# Robot_Led_Stripe_1_25mm.net
KiCad netlist of a schematic drawn in EasyEDA
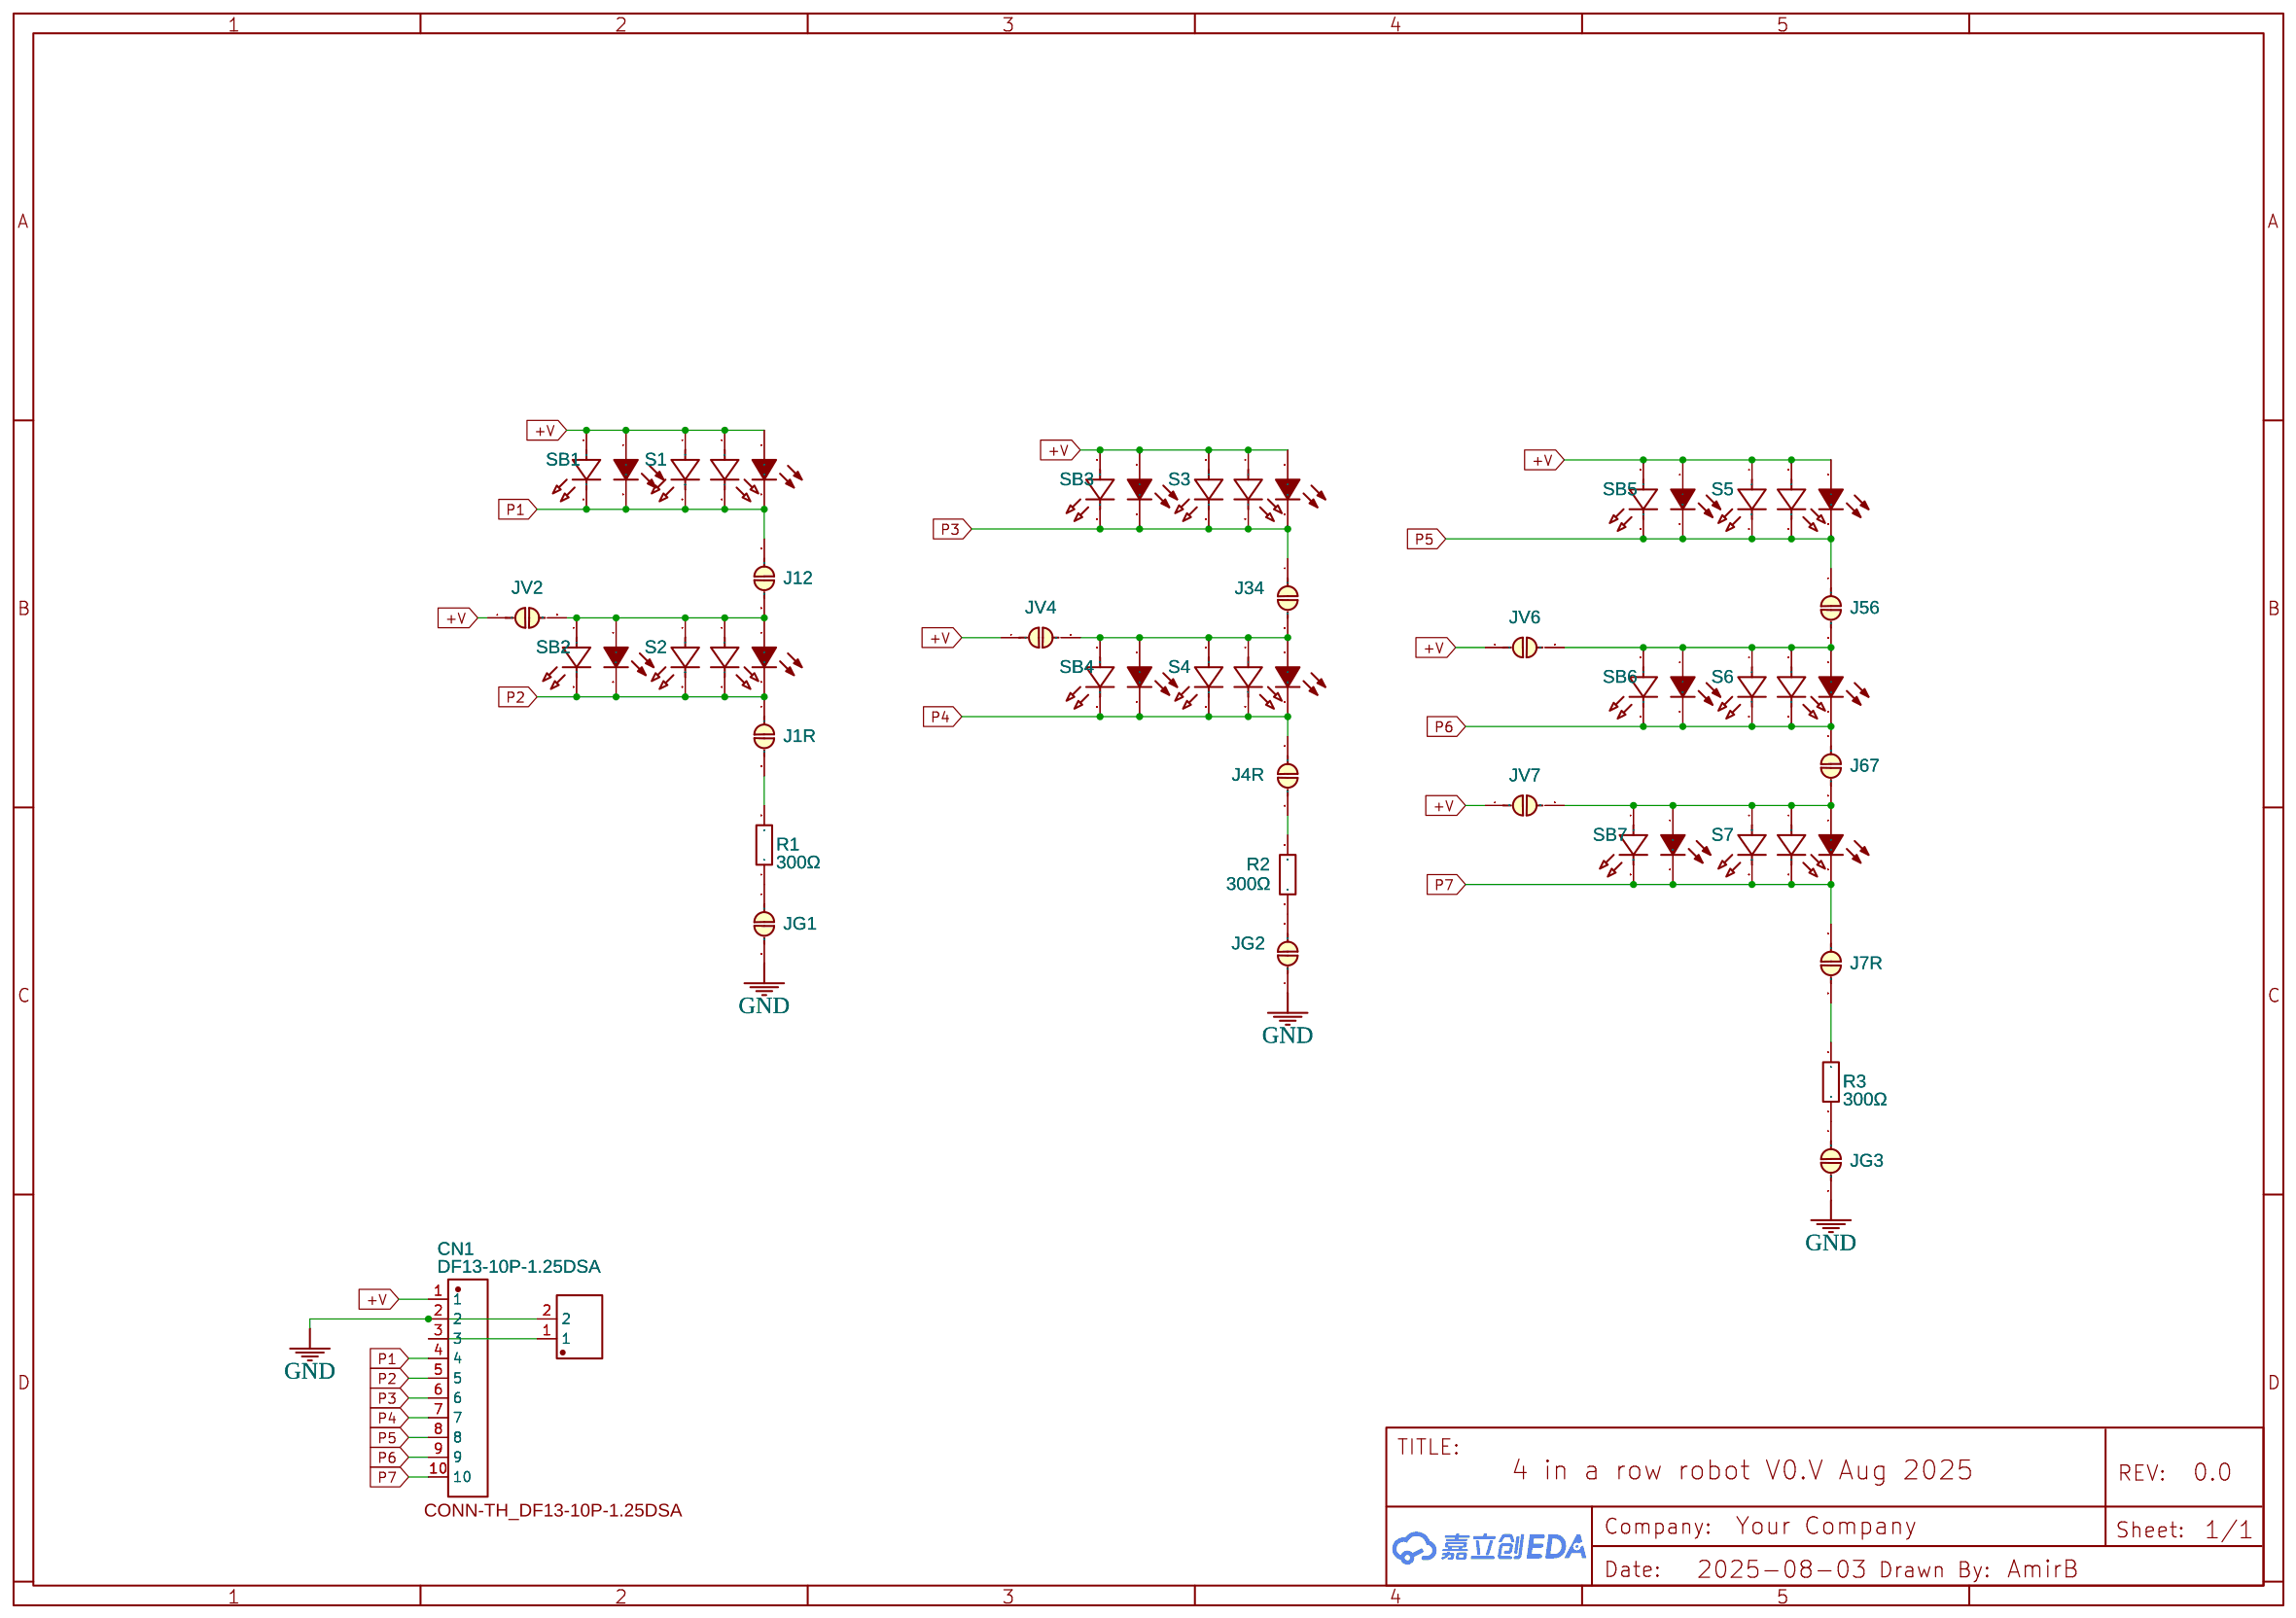
[diagram p0: schematic sheet]

(export (version "E")
  (design (tool "Eeschema 10.0.6"))
  (components
    (comp (ref "CN1")
      (value "DF13-10P-1.25DSA")
      (fields (field (name "Manufacturer") "HRS(广濑)"))
      (libsource (lib "") (part "DF13-10P-1.25DSA"))
    )
    (comp (ref "ECON1")
      (value "KF2510-2A")
      (fields (field (name "BOM_Supplier Part") "C27543"))
      (libsource (lib "") (part "KF2510-2A"))
    )
    (comp (ref "J1R") (value "J1R") (libsource (lib "") (part "JUMPER-SMT_2_5")))
    (comp (ref "J4R") (value "J4R") (libsource (lib "") (part "JUMPER-SMT_2_4")))
    (comp (ref "J7R") (value "J7R") (libsource (lib "") (part "JUMPER-SMT_2_3")))
    (comp (ref "J12") (value "J1") (libsource (lib "") (part "JUMPER-SMT_2_1")))
    (comp (ref "J34") (value "J34") (libsource (lib "") (part "JUMPER-SMT_2_1")))
    (comp (ref "J56") (value "J56") (libsource (lib "") (part "JUMPER-SMT_2_1")))
    (comp (ref "J67") (value "J67") (libsource (lib "") (part "JUMPER-SMT_2_1")))
    (comp (ref "JG1") (value "JG3") (libsource (lib "") (part "JUMPER-SMT_2_2")))
    (comp (ref "JG2") (value "JG3") (libsource (lib "") (part "JUMPER-SMT_2_2")))
    (comp (ref "JG3") (value "JG3") (libsource (lib "") (part "JUMPER-SMT_2_2")))
    (comp (ref "JV2") (value "JV1") (libsource (lib "") (part "JUMPER-SMT_2")))
    (comp (ref "JV4") (value "JV1") (libsource (lib "") (part "JUMPER-SMT_2")))
    (comp (ref "JV6") (value "JV1") (libsource (lib "") (part "JUMPER-SMT_2")))
    (comp (ref "JV7") (value "JV1") (libsource (lib "") (part "JUMPER-SMT_2")))
    (comp (ref "L1")
      (value "LED")
      (fields
        (field (name "BOM_Manufacturer Part") "19-217/BHC-ZL1M2RY/3T")
        (field (name "BOM_Supplier Part") "C72041")
      )
      (libsource (lib "") (part "19-217/BHC-ZL1M2RY/3T"))
    )
    (comp (ref "L2")
      (value "LED")
      (fields
        (field (name "BOM_Manufacturer Part") "19-217/BHC-ZL1M2RY/3T")
        (field (name "BOM_Supplier Part") "C72041")
      )
      (libsource (lib "") (part "19-217/BHC-ZL1M2RY/3T"))
    )
    (comp (ref "L3")
      (value "LED")
      (fields
        (field (name "BOM_Manufacturer Part") "19-217/BHC-ZL1M2RY/3T")
        (field (name "BOM_Supplier Part") "C72041")
      )
      (libsource (lib "") (part "19-217/BHC-ZL1M2RY/3T"))
    )
    (comp (ref "L4")
      (value "LED")
      (fields
        (field (name "BOM_Manufacturer Part") "19-217/BHC-ZL1M2RY/3T")
        (field (name "BOM_Supplier Part") "C72041")
      )
      (libsource (lib "") (part "19-217/BHC-ZL1M2RY/3T"))
    )
    (comp (ref "L5")
      (value "LED")
      (fields
        (field (name "BOM_Manufacturer Part") "19-217/BHC-ZL1M2RY/3T")
        (field (name "BOM_Supplier Part") "C72041")
      )
      (libsource (lib "") (part "19-217/BHC-ZL1M2RY/3T"))
    )
    (comp (ref "L6")
      (value "LED")
      (fields
        (field (name "BOM_Manufacturer Part") "19-217/BHC-ZL1M2RY/3T")
        (field (name "BOM_Supplier Part") "C72041")
      )
      (libsource (lib "") (part "19-217/BHC-ZL1M2RY/3T"))
    )
    (comp (ref "L7")
      (value "LED")
      (fields
        (field (name "BOM_Manufacturer Part") "19-217/BHC-ZL1M2RY/3T")
        (field (name "BOM_Supplier Part") "C72041")
      )
      (libsource (lib "") (part "19-217/BHC-ZL1M2RY/3T"))
    )
    (comp (ref "LB1")
      (value "LED")
      (fields
        (field (name "BOM_Manufacturer Part") "19-217/BHC-ZL1M2RY/3T")
        (field (name "BOM_Supplier Part") "C72041")
      )
      (libsource (lib "") (part "19-217/BHC-ZL1M2RY/3T_1"))
    )
    (comp (ref "LB2")
      (value "LED")
      (fields
        (field (name "BOM_Manufacturer Part") "19-217/BHC-ZL1M2RY/3T")
        (field (name "BOM_Supplier Part") "C72041")
      )
      (libsource (lib "") (part "19-217/BHC-ZL1M2RY/3T_1"))
    )
    (comp (ref "LB3")
      (value "LED")
      (fields
        (field (name "BOM_Manufacturer Part") "19-217/BHC-ZL1M2RY/3T")
        (field (name "BOM_Supplier Part") "C72041")
      )
      (libsource (lib "") (part "19-217/BHC-ZL1M2RY/3T_1"))
    )
    (comp (ref "LB4")
      (value "LED")
      (fields
        (field (name "BOM_Manufacturer Part") "19-217/BHC-ZL1M2RY/3T")
        (field (name "BOM_Supplier Part") "C72041")
      )
      (libsource (lib "") (part "19-217/BHC-ZL1M2RY/3T_1"))
    )
    (comp (ref "LB5")
      (value "LED")
      (fields
        (field (name "BOM_Manufacturer Part") "19-217/BHC-ZL1M2RY/3T")
        (field (name "BOM_Supplier Part") "C72041")
      )
      (libsource (lib "") (part "19-217/BHC-ZL1M2RY/3T_1"))
    )
    (comp (ref "LB6")
      (value "LED")
      (fields
        (field (name "BOM_Manufacturer Part") "19-217/BHC-ZL1M2RY/3T")
        (field (name "BOM_Supplier Part") "C72041")
      )
      (libsource (lib "") (part "19-217/BHC-ZL1M2RY/3T_1"))
    )
    (comp (ref "LB7")
      (value "LED")
      (fields
        (field (name "BOM_Manufacturer Part") "19-217/BHC-ZL1M2RY/3T")
        (field (name "BOM_Supplier Part") "C72041")
      )
      (libsource (lib "") (part "19-217/BHC-ZL1M2RY/3T_1"))
    )
    (comp (ref "R1")
      (value "300Ω")
      (fields
        (field (name "Manufacturer Part") "0603WAF3000T5E")
        (field (name "Manufacturer") "UNI-ROYAL(厚声)")
      )
      (libsource (lib "") (part "0603WAF3000T5E"))
    )
    (comp (ref "R2")
      (value "300Ω")
      (fields
        (field (name "Manufacturer Part") "0603WAF3000T5E")
        (field (name "Manufacturer") "UNI-ROYAL(厚声)")
      )
      (libsource (lib "") (part "0603WAF3000T5E"))
    )
    (comp (ref "R3")
      (value "300Ω")
      (fields
        (field (name "Manufacturer Part") "0603WAF3000T5E")
        (field (name "Manufacturer") "UNI-ROYAL(厚声)")
      )
      (libsource (lib "") (part "0603WAF3000T5E"))
    )
    (comp (ref "S1")
      (value "XYC-PT3528AC-IC")
      (fields (field (name "Manufacturer") "NEWOPTO(鑫永诚光电)"))
      (libsource (lib "") (part "XYC-PT3528AC-IC"))
    )
    (comp (ref "S2")
      (value "XYC-PT3528AC-IC")
      (fields (field (name "Manufacturer") "NEWOPTO(鑫永诚光电)"))
      (libsource (lib "") (part "XYC-PT3528AC-IC"))
    )
    (comp (ref "S3")
      (value "XYC-PT3528AC-IC")
      (fields (field (name "Manufacturer") "NEWOPTO(鑫永诚光电)"))
      (libsource (lib "") (part "XYC-PT3528AC-IC"))
    )
    (comp (ref "S4")
      (value "XYC-PT3528AC-IC")
      (fields (field (name "Manufacturer") "NEWOPTO(鑫永诚光电)"))
      (libsource (lib "") (part "XYC-PT3528AC-IC"))
    )
    (comp (ref "S5")
      (value "XYC-PT3528AC-IC")
      (fields (field (name "Manufacturer") "NEWOPTO(鑫永诚光电)"))
      (libsource (lib "") (part "XYC-PT3528AC-IC"))
    )
    (comp (ref "S6")
      (value "XYC-PT3528AC-IC")
      (fields (field (name "Manufacturer") "NEWOPTO(鑫永诚光电)"))
      (libsource (lib "") (part "XYC-PT3528AC-IC"))
    )
    (comp (ref "S7")
      (value "XYC-PT3528AC-IC")
      (fields (field (name "Manufacturer") "NEWOPTO(鑫永诚光电)"))
      (libsource (lib "") (part "XYC-PT3528AC-IC"))
    )
    (comp (ref "SB1")
      (value "XYC-PT3528AC-IC")
      (fields (field (name "Manufacturer") "NEWOPTO(鑫永诚光电)"))
      (libsource (lib "") (part "XYC-PT3528AC-IC_1"))
    )
    (comp (ref "SB2")
      (value "XYC-PT3528AC-IC")
      (fields (field (name "Manufacturer") "NEWOPTO(鑫永诚光电)"))
      (libsource (lib "") (part "XYC-PT3528AC-IC_1"))
    )
    (comp (ref "SB3")
      (value "XYC-PT3528AC-IC")
      (fields (field (name "Manufacturer") "NEWOPTO(鑫永诚光电)"))
      (libsource (lib "") (part "XYC-PT3528AC-IC_1"))
    )
    (comp (ref "SB4")
      (value "XYC-PT3528AC-IC")
      (fields (field (name "Manufacturer") "NEWOPTO(鑫永诚光电)"))
      (libsource (lib "") (part "XYC-PT3528AC-IC_1"))
    )
    (comp (ref "SB5")
      (value "XYC-PT3528AC-IC")
      (fields (field (name "Manufacturer") "NEWOPTO(鑫永诚光电)"))
      (libsource (lib "") (part "XYC-PT3528AC-IC_1"))
    )
    (comp (ref "SB6")
      (value "XYC-PT3528AC-IC")
      (fields (field (name "Manufacturer") "NEWOPTO(鑫永诚光电)"))
      (libsource (lib "") (part "XYC-PT3528AC-IC_1"))
    )
    (comp (ref "SB7")
      (value "XYC-PT3528AC-IC")
      (fields (field (name "Manufacturer") "NEWOPTO(鑫永诚光电)"))
      (libsource (lib "") (part "XYC-PT3528AC-IC_1"))
    )
    (comp (ref "U1") (value "L240CTZ0G3MM") (libsource (lib "") (part "L240CTZ0G3MM")))
    (comp (ref "U2") (value "L240CTZ0G3MM") (libsource (lib "") (part "L240CTZ0G3MM")))
    (comp (ref "U3") (value "L240CTZ0G3MM") (libsource (lib "") (part "L240CTZ0G3MM")))
    (comp (ref "U4") (value "L240CTZ0G3MM") (libsource (lib "") (part "L240CTZ0G3MM")))
    (comp (ref "U5") (value "L240CTZ0G3MM") (libsource (lib "") (part "L240CTZ0G3MM")))
    (comp (ref "U6") (value "L240CTZ0G3MM") (libsource (lib "") (part "L240CTZ0G3MM")))
    (comp (ref "U7") (value "L240CTZ0G3MM") (libsource (lib "") (part "L240CTZ0G3MM")))
  )
  (nets
    (net (code "1") (name "+V") (class "Default")
      (node (ref "CN1") (pin "1") (pinfunction "1_1") (pintype "unspecified"))
      (node (ref "JV2") (pin "1") (pinfunction "1_1") (pintype "bidirectional"))
      (node (ref "JV4") (pin "1") (pinfunction "1_1") (pintype "bidirectional"))
      (node (ref "JV6") (pin "1") (pinfunction "1_1") (pintype "bidirectional"))
      (node (ref "JV7") (pin "1") (pinfunction "1_1") (pintype "bidirectional"))
      (node (ref "L1") (pin "1") (pinfunction "A_1") (pintype "input"))
      (node (ref "L3") (pin "1") (pinfunction "A_1") (pintype "input"))
      (node (ref "L5") (pin "1") (pinfunction "A_1") (pintype "input"))
      (node (ref "LB1") (pin "1") (pinfunction "A_1") (pintype "input"))
      (node (ref "LB3") (pin "1") (pinfunction "A_1") (pintype "input"))
      (node (ref "LB5") (pin "1") (pinfunction "A_1") (pintype "input"))
      (node (ref "S1") (pin "1") (pinfunction "1_1") (pintype "unspecified"))
      (node (ref "S3") (pin "1") (pinfunction "1_1") (pintype "unspecified"))
      (node (ref "S5") (pin "1") (pinfunction "1_1") (pintype "unspecified"))
      (node (ref "SB1") (pin "1") (pinfunction "1_1") (pintype "unspecified"))
      (node (ref "SB3") (pin "1") (pinfunction "1_1") (pintype "unspecified"))
      (node (ref "SB5") (pin "1") (pinfunction "1_1") (pintype "unspecified"))
      (node (ref "U1") (pin "1") (pinfunction "A_1") (pintype "unspecified"))
      (node (ref "U3") (pin "1") (pinfunction "A_1") (pintype "unspecified"))
      (node (ref "U5") (pin "1") (pinfunction "A_1") (pintype "unspecified"))
    )
    (net (code "2") (name "GND") (class "Default")
      (node (ref "CN1") (pin "2") (pinfunction "2_2") (pintype "unspecified"))
      (node (ref "ECON1") (pin "2") (pinfunction "2_2") (pintype "unspecified"))
      (node (ref "JG1") (pin "2") (pinfunction "2_2") (pintype "bidirectional"))
      (node (ref "JG2") (pin "2") (pinfunction "2_2") (pintype "bidirectional"))
      (node (ref "JG3") (pin "2") (pinfunction "2_2") (pintype "bidirectional"))
    )
    (net (code "3") (name "Net-(CN1-Pad3)") (class "Default")
      (node (ref "CN1") (pin "3") (pinfunction "3_3") (pintype "unspecified"))
      (node (ref "ECON1") (pin "1") (pinfunction "1_1") (pintype "unspecified"))
    )
    (net (code "4") (name "Net-(J1R-Pad2)") (class "Default")
      (node (ref "J1R") (pin "2") (pinfunction "2_2") (pintype "bidirectional"))
      (node (ref "R1") (pin "2") (pinfunction "2_2") (pintype "input"))
    )
    (net (code "5") (name "Net-(J4R-Pad2)") (class "Default")
      (node (ref "J4R") (pin "2") (pinfunction "2_2") (pintype "bidirectional"))
      (node (ref "R2") (pin "2") (pinfunction "2_2") (pintype "input"))
    )
    (net (code "6") (name "Net-(J7R-Pad2)") (class "Default")
      (node (ref "J7R") (pin "2") (pinfunction "2_2") (pintype "bidirectional"))
      (node (ref "R3") (pin "2") (pinfunction "2_2") (pintype "input"))
    )
    (net (code "7") (name "Net-(JG1-Pad1)") (class "Default")
      (node (ref "JG1") (pin "1") (pinfunction "1_1") (pintype "bidirectional"))
      (node (ref "R1") (pin "1") (pinfunction "1_1") (pintype "input"))
    )
    (net (code "8") (name "Net-(JG2-Pad1)") (class "Default")
      (node (ref "JG2") (pin "1") (pinfunction "1_1") (pintype "bidirectional"))
      (node (ref "R2") (pin "1") (pinfunction "1_1") (pintype "input"))
    )
    (net (code "9") (name "Net-(JG3-Pad1)") (class "Default")
      (node (ref "JG3") (pin "1") (pinfunction "1_1") (pintype "bidirectional"))
      (node (ref "R3") (pin "1") (pinfunction "1_1") (pintype "input"))
    )
    (net (code "10") (name "Net-(L2-A)") (class "Default")
      (node (ref "J12") (pin "2") (pinfunction "2_2") (pintype "bidirectional"))
      (node (ref "JV2") (pin "2") (pinfunction "2_2") (pintype "bidirectional"))
      (node (ref "L2") (pin "1") (pinfunction "A_1") (pintype "input"))
      (node (ref "LB2") (pin "1") (pinfunction "A_1") (pintype "input"))
      (node (ref "S2") (pin "1") (pinfunction "1_1") (pintype "unspecified"))
      (node (ref "SB2") (pin "1") (pinfunction "1_1") (pintype "unspecified"))
      (node (ref "U2") (pin "1") (pinfunction "A_1") (pintype "unspecified"))
    )
    (net (code "11") (name "Net-(L4-A)") (class "Default")
      (node (ref "J34") (pin "2") (pinfunction "2_2") (pintype "bidirectional"))
      (node (ref "JV4") (pin "2") (pinfunction "2_2") (pintype "bidirectional"))
      (node (ref "L4") (pin "1") (pinfunction "A_1") (pintype "input"))
      (node (ref "LB4") (pin "1") (pinfunction "A_1") (pintype "input"))
      (node (ref "S4") (pin "1") (pinfunction "1_1") (pintype "unspecified"))
      (node (ref "SB4") (pin "1") (pinfunction "1_1") (pintype "unspecified"))
      (node (ref "U4") (pin "1") (pinfunction "A_1") (pintype "unspecified"))
    )
    (net (code "12") (name "Net-(L6-A)") (class "Default")
      (node (ref "J56") (pin "2") (pinfunction "2_2") (pintype "bidirectional"))
      (node (ref "JV6") (pin "2") (pinfunction "2_2") (pintype "bidirectional"))
      (node (ref "L6") (pin "1") (pinfunction "A_1") (pintype "input"))
      (node (ref "LB6") (pin "1") (pinfunction "A_1") (pintype "input"))
      (node (ref "S6") (pin "1") (pinfunction "1_1") (pintype "unspecified"))
      (node (ref "SB6") (pin "1") (pinfunction "1_1") (pintype "unspecified"))
      (node (ref "U6") (pin "1") (pinfunction "A_1") (pintype "unspecified"))
    )
    (net (code "13") (name "Net-(L7-A)") (class "Default")
      (node (ref "J67") (pin "2") (pinfunction "2_2") (pintype "bidirectional"))
      (node (ref "JV7") (pin "2") (pinfunction "2_2") (pintype "bidirectional"))
      (node (ref "L7") (pin "1") (pinfunction "A_1") (pintype "input"))
      (node (ref "LB7") (pin "1") (pinfunction "A_1") (pintype "input"))
      (node (ref "S7") (pin "1") (pinfunction "1_1") (pintype "unspecified"))
      (node (ref "SB7") (pin "1") (pinfunction "1_1") (pintype "unspecified"))
      (node (ref "U7") (pin "1") (pinfunction "A_1") (pintype "unspecified"))
    )
    (net (code "14") (name "P1") (class "Default")
      (node (ref "CN1") (pin "4") (pinfunction "4_4") (pintype "unspecified"))
      (node (ref "J12") (pin "1") (pinfunction "1_1") (pintype "bidirectional"))
      (node (ref "L1") (pin "2") (pinfunction "C_2") (pintype "input"))
      (node (ref "LB1") (pin "2") (pinfunction "C_2") (pintype "input"))
      (node (ref "S1") (pin "2") (pinfunction "2_2") (pintype "unspecified"))
      (node (ref "SB1") (pin "2") (pinfunction "2_2") (pintype "unspecified"))
      (node (ref "U1") (pin "2") (pinfunction "K_2") (pintype "unspecified"))
    )
    (net (code "15") (name "P2") (class "Default")
      (node (ref "CN1") (pin "5") (pinfunction "5_5") (pintype "unspecified"))
      (node (ref "J1R") (pin "1") (pinfunction "1_1") (pintype "bidirectional"))
      (node (ref "L2") (pin "2") (pinfunction "C_2") (pintype "input"))
      (node (ref "LB2") (pin "2") (pinfunction "C_2") (pintype "input"))
      (node (ref "S2") (pin "2") (pinfunction "2_2") (pintype "unspecified"))
      (node (ref "SB2") (pin "2") (pinfunction "2_2") (pintype "unspecified"))
      (node (ref "U2") (pin "2") (pinfunction "K_2") (pintype "unspecified"))
    )
    (net (code "16") (name "P3") (class "Default")
      (node (ref "CN1") (pin "6") (pinfunction "6_6") (pintype "unspecified"))
      (node (ref "J34") (pin "1") (pinfunction "1_1") (pintype "bidirectional"))
      (node (ref "L3") (pin "2") (pinfunction "C_2") (pintype "input"))
      (node (ref "LB3") (pin "2") (pinfunction "C_2") (pintype "input"))
      (node (ref "S3") (pin "2") (pinfunction "2_2") (pintype "unspecified"))
      (node (ref "SB3") (pin "2") (pinfunction "2_2") (pintype "unspecified"))
      (node (ref "U3") (pin "2") (pinfunction "K_2") (pintype "unspecified"))
    )
    (net (code "17") (name "P4") (class "Default")
      (node (ref "CN1") (pin "7") (pinfunction "7_7") (pintype "unspecified"))
      (node (ref "J4R") (pin "1") (pinfunction "1_1") (pintype "bidirectional"))
      (node (ref "L4") (pin "2") (pinfunction "C_2") (pintype "input"))
      (node (ref "LB4") (pin "2") (pinfunction "C_2") (pintype "input"))
      (node (ref "S4") (pin "2") (pinfunction "2_2") (pintype "unspecified"))
      (node (ref "SB4") (pin "2") (pinfunction "2_2") (pintype "unspecified"))
      (node (ref "U4") (pin "2") (pinfunction "K_2") (pintype "unspecified"))
    )
    (net (code "18") (name "P5") (class "Default")
      (node (ref "CN1") (pin "8") (pinfunction "8_8") (pintype "unspecified"))
      (node (ref "J56") (pin "1") (pinfunction "1_1") (pintype "bidirectional"))
      (node (ref "L5") (pin "2") (pinfunction "C_2") (pintype "input"))
      (node (ref "LB5") (pin "2") (pinfunction "C_2") (pintype "input"))
      (node (ref "S5") (pin "2") (pinfunction "2_2") (pintype "unspecified"))
      (node (ref "SB5") (pin "2") (pinfunction "2_2") (pintype "unspecified"))
      (node (ref "U5") (pin "2") (pinfunction "K_2") (pintype "unspecified"))
    )
    (net (code "19") (name "P6") (class "Default")
      (node (ref "CN1") (pin "9") (pinfunction "9_9") (pintype "unspecified"))
      (node (ref "J67") (pin "1") (pinfunction "1_1") (pintype "bidirectional"))
      (node (ref "L6") (pin "2") (pinfunction "C_2") (pintype "input"))
      (node (ref "LB6") (pin "2") (pinfunction "C_2") (pintype "input"))
      (node (ref "S6") (pin "2") (pinfunction "2_2") (pintype "unspecified"))
      (node (ref "SB6") (pin "2") (pinfunction "2_2") (pintype "unspecified"))
      (node (ref "U6") (pin "2") (pinfunction "K_2") (pintype "unspecified"))
    )
    (net (code "20") (name "P7") (class "Default")
      (node (ref "CN1") (pin "10") (pinfunction "10_10") (pintype "unspecified"))
      (node (ref "J7R") (pin "1") (pinfunction "1_1") (pintype "bidirectional"))
      (node (ref "L7") (pin "2") (pinfunction "C_2") (pintype "input"))
      (node (ref "LB7") (pin "2") (pinfunction "C_2") (pintype "input"))
      (node (ref "S7") (pin "2") (pinfunction "2_2") (pintype "unspecified"))
      (node (ref "SB7") (pin "2") (pinfunction "2_2") (pintype "unspecified"))
      (node (ref "U7") (pin "2") (pinfunction "K_2") (pintype "unspecified"))
    )
  )
)
